# avr_programming_shield_v2.net
KiCad netlist of a schematic drawn in EAGLE
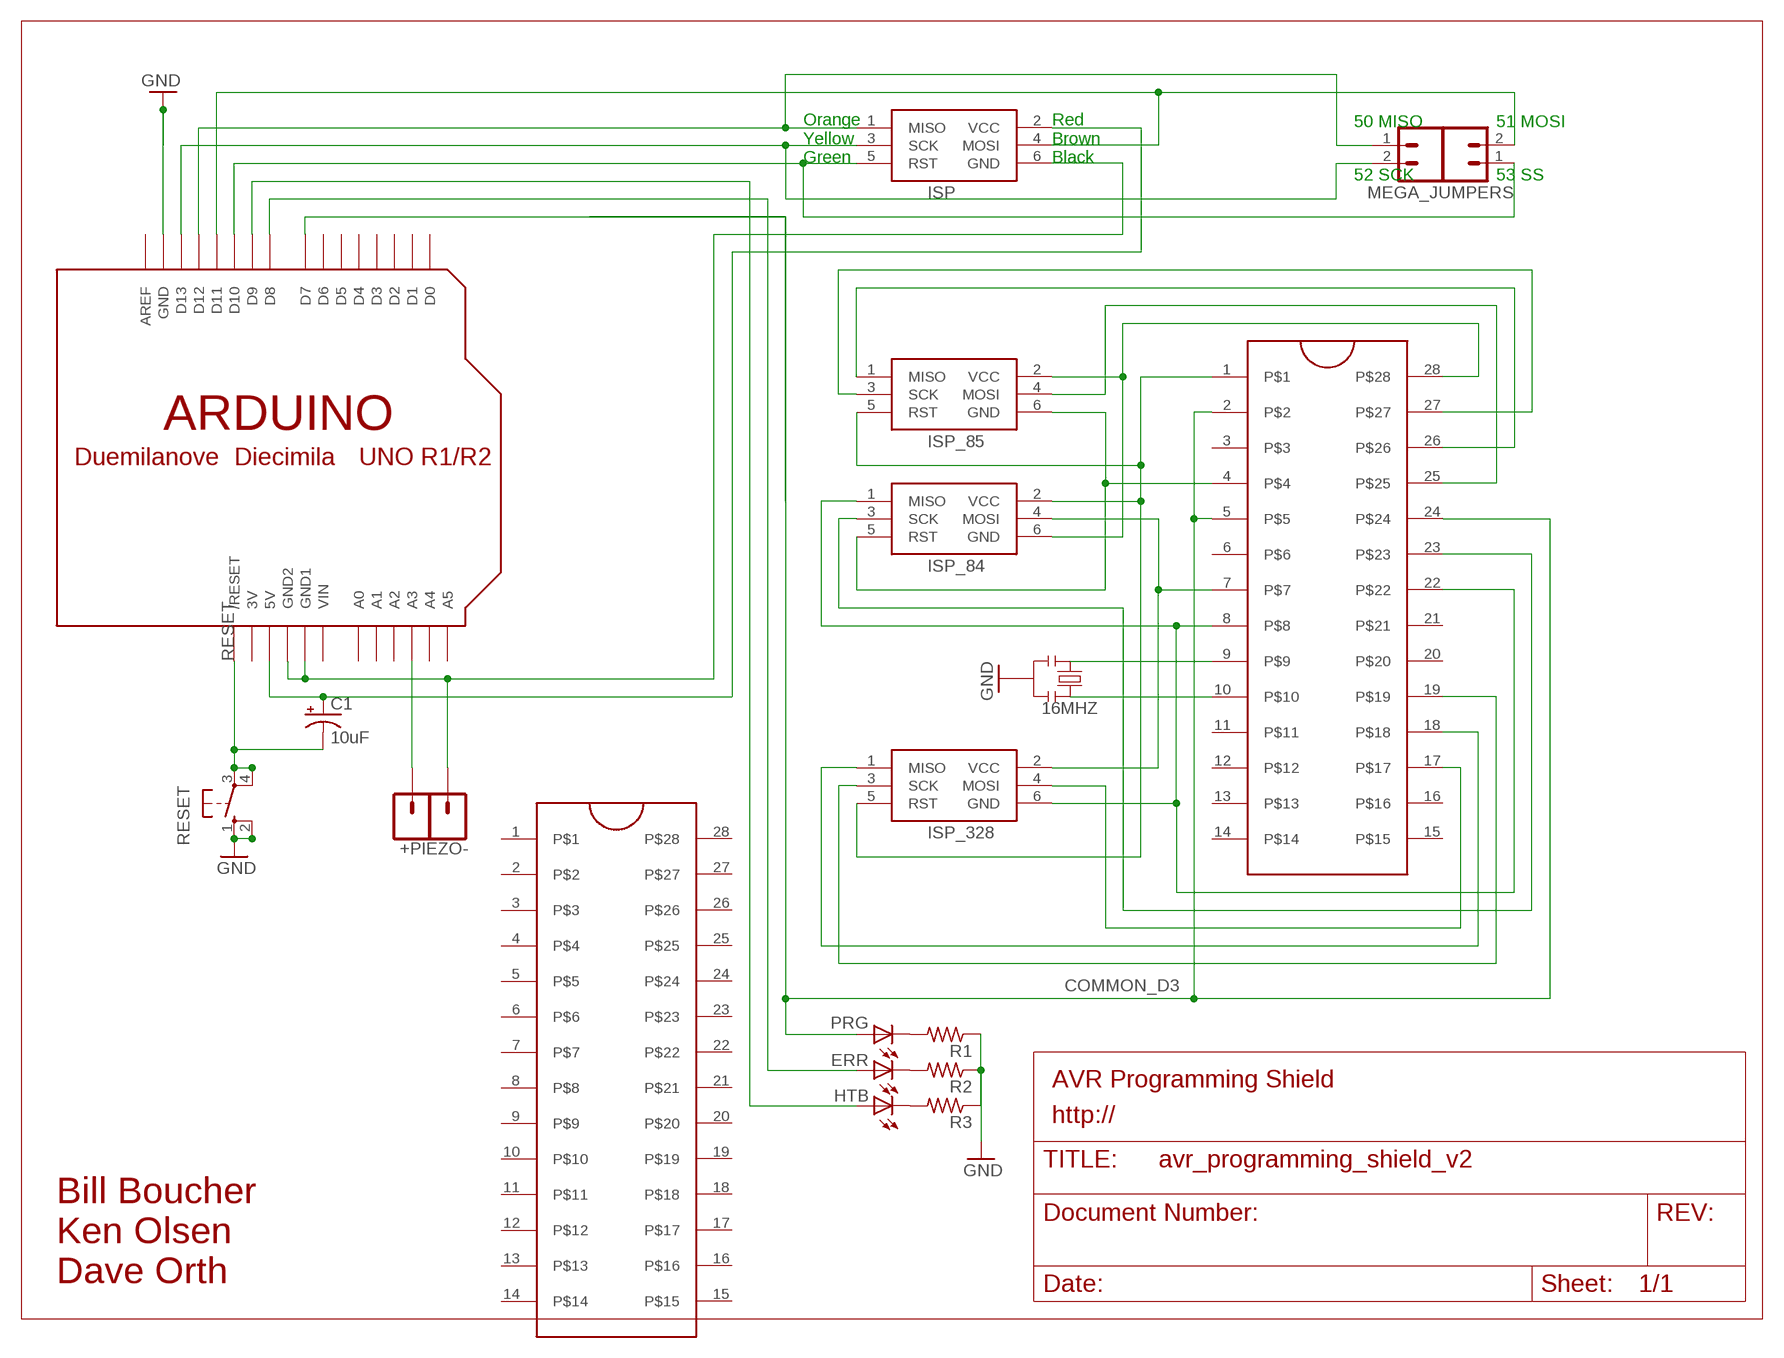
[diagram p0: schematic, sheet 1]

(export (version "E")
  (design (tool "Eeschema 10.0.6"))
  (components
    (comp (ref "+PIEZO-")
      (value "M01PTH")
      (footprint "eagle-import:1X01")
      (libsource (lib "eagle-import") (part "M01PTH"))
    )
    (comp (ref "16MHZ")
      (value "RESONATORPTH")
      (footprint "eagle-import:RESONATOR-PTH")
      (libsource (lib "eagle-import") (part "RESONATORPTH"))
    )
    (comp (ref "C1")
      (value "10uF")
      (footprint "eagle-import:CPOL-RADIAL-10UF-25V")
      (fields (field (name "MF") "ILLINOIS CAPACITOR,INC.") (field (name "MPN") "106TTA035M"))
      (libsource (lib "eagle-import") (part "CAP_POLPTH2"))
    )
    (comp (ref "ERR")
      (value "LED3MM")
      (footprint "eagle-import:LED3MM")
      (libsource (lib "eagle-import") (part "LED3MM"))
    )
    (comp (ref "HTB")
      (value "LED3MM")
      (footprint "eagle-import:LED3MM")
      (libsource (lib "eagle-import") (part "LED3MM"))
    )
    (comp (ref "ISP")
      (value "AVRISP-6")
      (footprint "eagle-import:AVRISP")
      (libsource (lib "eagle-import") (part "AVRISP-6"))
    )
    (comp (ref "ISP_84")
      (value "AVRISP-6")
      (footprint "eagle-import:AVRISP")
      (libsource (lib "eagle-import") (part "AVRISP-6"))
    )
    (comp (ref "ISP_85")
      (value "AVRISP-6")
      (footprint "eagle-import:AVRISP")
      (libsource (lib "eagle-import") (part "AVRISP-6"))
    )
    (comp (ref "ISP_328")
      (value "AVRISP-6")
      (footprint "eagle-import:AVRISP")
      (libsource (lib "eagle-import") (part "AVRISP-6"))
    )
    (comp (ref "JP2")
      (value "M02PTH")
      (footprint "eagle-import:1X02")
      (libsource (lib "eagle-import") (part "M02PTH"))
    )
    (comp (ref "JP4")
      (value "M01PTH")
      (footprint "eagle-import:1X01")
      (libsource (lib "eagle-import") (part "M01PTH"))
    )
    (comp (ref "MEGA_JUMPERS")
      (value "M02PTH")
      (footprint "eagle-import:1X02")
      (libsource (lib "eagle-import") (part "M02PTH"))
    )
    (comp (ref "PRG")
      (value "LED3MM")
      (footprint "eagle-import:LED3MM")
      (libsource (lib "eagle-import") (part "LED3MM"))
    )
    (comp (ref "R1")
      (value "R-US_0204/2V")
      (footprint "eagle-import:0204V")
      (libsource (lib "eagle-import") (part "R-US_0204/2V"))
    )
    (comp (ref "R2")
      (value "R-US_0204/2V")
      (footprint "eagle-import:0204V")
      (libsource (lib "eagle-import") (part "R-US_0204/2V"))
    )
    (comp (ref "R3")
      (value "R-US_0204/2V")
      (footprint "eagle-import:0204V")
      (libsource (lib "eagle-import") (part "R-US_0204/2V"))
    )
    (comp (ref "RESET")
      (value "10-XX")
      (footprint "eagle-import:B3F-10XX")
      (fields
        (field (name "MPN") "B3F-1000")
        (field (name "MPN_1") "B3F-1000")
        (field (name "OC_NEWARK") "36M3542")
      )
      (libsource (lib "eagle-import") (part "10-XX"))
    )
    (comp (ref "U$1")
      (value "ARDUINO-NOHOLE")
      (footprint "eagle-import:ARDUINO-NOHOLE")
      (libsource (lib "eagle-import") (part "ARDUINO-NOHOLE"))
    )
    (comp (ref "U$3")
      (value "ZIFSOCKET-28-3ZIFFSOCKET-28-3")
      (footprint "eagle-import:DIL28-3-ZIF_SOCKET")
      (libsource (lib "eagle-import") (part "ZIFSOCKET-28-3ZIFFSOCKET-28-3"))
    )
    (comp (ref "U$4")
      (value "ZIFSOCKET-28-3ZIFFSOCKET-28-3")
      (footprint "eagle-import:DIL28-3-ZIF_SOCKET")
      (libsource (lib "eagle-import") (part "SparkFun_mod_ZIFSOCKET-28-3ZIFFSOCKET-28-3"))
    )
  )
  (nets
    (net (code "1") (name "/3V") (class "Default")
      (node (ref "U$1") (pin "3V") (pinfunction "3V_3V") (pintype "power_in"))
    )
    (net (code "2") (name "/COMMON_D3") (class "Default")
      (node (ref "PRG") (pin "A") (pinfunction "A_A") (pintype "passive"))
      (node (ref "U$1") (pin "D7") (pinfunction "D7_D7") (pintype "bidirectional"))
      (node (ref "U$4") (pin "2") (pinfunction "P$2_2") (pintype "bidirectional"))
      (node (ref "U$4") (pin "24") (pinfunction "P$24_24") (pintype "bidirectional"))
      (node (ref "U$4") (pin "5") (pinfunction "P$5_5") (pintype "bidirectional"))
    )
    (net (code "3") (name "/RESET") (class "Default")
      (node (ref "C1") (pin "2") (pinfunction "-_2") (pintype "passive"))
      (node (ref "RESET") (pin "3") (pinfunction "P_3") (pintype "passive"))
      (node (ref "RESET") (pin "4") (pinfunction "P1_4") (pintype "passive"))
      (node (ref "U$1") (pin "RESET") (pinfunction "/RESET_RESET") (pintype "bidirectional"))
    )
    (net (code "4") (name "/VIN") (class "Default")
      (node (ref "U$1") (pin "VIN") (pinfunction "VIN_VIN") (pintype "power_in"))
    )
    (net (code "5") (name "GND") (class "Default")
      (node (ref "+PIEZO-") (pin "1") (pinfunction "1_1") (pintype "passive"))
      (node (ref "16MHZ") (pin "2") (pinfunction "2_2") (pintype "passive"))
      (node (ref "ISP") (pin "6") (pinfunction "GND_6") (pintype "power_in"))
      (node (ref "R1") (pin "1") (pinfunction "1_1") (pintype "passive"))
      (node (ref "R2") (pin "1") (pinfunction "1_1") (pintype "passive"))
      (node (ref "R3") (pin "1") (pinfunction "1_1") (pintype "passive"))
      (node (ref "RESET") (pin "1") (pinfunction "S_1") (pintype "passive"))
      (node (ref "RESET") (pin "2") (pinfunction "S1_2") (pintype "passive"))
      (node (ref "U$1") (pin "GND") (pinfunction "GND_GND") (pintype "power_in"))
      (node (ref "U$1") (pin "GND1") (pinfunction "GND1_GND1") (pintype "power_in"))
      (node (ref "U$1") (pin "GND2") (pinfunction "GND2_GND2") (pintype "power_in"))
    )
    (net (code "6") (name "Net-(C1-+)") (class "Default")
      (node (ref "C1") (pin "1") (pinfunction "+_1") (pintype "passive"))
      (node (ref "ISP") (pin "2") (pinfunction "VCC_2") (pintype "power_in"))
      (node (ref "U$1") (pin "5V") (pinfunction "5V_5V") (pintype "power_in"))
    )
    (net (code "7") (name "Net-(ERR-C)") (class "Default")
      (node (ref "ERR") (pin "K") (pinfunction "C_K") (pintype "passive"))
      (node (ref "R2") (pin "2") (pinfunction "2_2") (pintype "passive"))
    )
    (net (code "8") (name "Net-(ERR-PadA)") (class "Default")
      (node (ref "ERR") (pin "A") (pinfunction "A_A") (pintype "passive"))
      (node (ref "U$1") (pin "D8") (pinfunction "D8_D8") (pintype "bidirectional"))
    )
    (net (code "9") (name "Net-(HTB-C)") (class "Default")
      (node (ref "HTB") (pin "K") (pinfunction "C_K") (pintype "passive"))
      (node (ref "R3") (pin "2") (pinfunction "2_2") (pintype "passive"))
    )
    (net (code "10") (name "Net-(HTB-PadA)") (class "Default")
      (node (ref "HTB") (pin "A") (pinfunction "A_A") (pintype "passive"))
      (node (ref "U$1") (pin "D9") (pinfunction "D9_D9") (pintype "bidirectional"))
    )
    (net (code "11") (name "Net-(ISP-MISO)") (class "Default")
      (node (ref "ISP") (pin "1") (pinfunction "MISO_1") (pintype "input"))
      (node (ref "MEGA_JUMPERS") (pin "1") (pinfunction "1_1") (pintype "passive"))
      (node (ref "U$1") (pin "D12") (pinfunction "D12_D12") (pintype "bidirectional"))
    )
    (net (code "12") (name "Net-(ISP-MOSI)") (class "Default")
      (node (ref "ISP") (pin "4") (pinfunction "MOSI_4") (pintype "output"))
      (node (ref "JP2") (pin "2") (pinfunction "2_2") (pintype "passive"))
      (node (ref "U$1") (pin "D11") (pinfunction "D11_D11") (pintype "bidirectional"))
    )
    (net (code "13") (name "Net-(ISP-RST)") (class "Default")
      (node (ref "ISP") (pin "5") (pinfunction "RST_5") (pintype "output"))
      (node (ref "JP2") (pin "1") (pinfunction "1_1") (pintype "passive"))
      (node (ref "U$1") (pin "D10") (pinfunction "D10_D10") (pintype "bidirectional"))
    )
    (net (code "14") (name "Net-(ISP-SCK)") (class "Default")
      (node (ref "ISP") (pin "3") (pinfunction "SCK_3") (pintype "output"))
      (node (ref "MEGA_JUMPERS") (pin "2") (pinfunction "2_2") (pintype "passive"))
      (node (ref "U$1") (pin "D13") (pinfunction "D13_D13") (pintype "bidirectional"))
    )
    (net (code "15") (name "Net-(ISP_84-GND)") (class "Default")
      (node (ref "ISP_84") (pin "6") (pinfunction "GND_6") (pintype "power_in"))
      (node (ref "ISP_85") (pin "2") (pinfunction "VCC_2") (pintype "power_in"))
      (node (ref "U$4") (pin "28") (pinfunction "P$28_28") (pintype "bidirectional"))
    )
    (net (code "16") (name "Net-(ISP_84-RST)") (class "Default")
      (node (ref "ISP_84") (pin "5") (pinfunction "RST_5") (pintype "output"))
      (node (ref "ISP_85") (pin "6") (pinfunction "GND_6") (pintype "power_in"))
      (node (ref "U$4") (pin "4") (pinfunction "P$4_4") (pintype "bidirectional"))
    )
    (net (code "17") (name "Net-(ISP_84-SCK)") (class "Default")
      (node (ref "ISP_84") (pin "3") (pinfunction "SCK_3") (pintype "output"))
      (node (ref "U$4") (pin "23") (pinfunction "P$23_23") (pintype "bidirectional"))
    )
    (net (code "18") (name "Net-(ISP_85-MISO)") (class "Default")
      (node (ref "ISP_85") (pin "1") (pinfunction "MISO_1") (pintype "input"))
      (node (ref "U$4") (pin "26") (pinfunction "P$26_26") (pintype "bidirectional"))
    )
    (net (code "19") (name "Net-(ISP_85-MOSI)") (class "Default")
      (node (ref "ISP_85") (pin "4") (pinfunction "MOSI_4") (pintype "output"))
      (node (ref "U$4") (pin "25") (pinfunction "P$25_25") (pintype "bidirectional"))
    )
    (net (code "20") (name "Net-(ISP_85-SCK)") (class "Default")
      (node (ref "ISP_85") (pin "3") (pinfunction "SCK_3") (pintype "output"))
      (node (ref "U$4") (pin "27") (pinfunction "P$27_27") (pintype "bidirectional"))
    )
    (net (code "21") (name "Net-(ISP_328-GND)") (class "Default")
      (node (ref "ISP_328") (pin "6") (pinfunction "GND_6") (pintype "power_in"))
      (node (ref "ISP_84") (pin "1") (pinfunction "MISO_1") (pintype "input"))
      (node (ref "U$4") (pin "22") (pinfunction "P$22_22") (pintype "bidirectional"))
      (node (ref "U$4") (pin "8") (pinfunction "P$8_8") (pintype "bidirectional"))
    )
    (net (code "22") (name "Net-(ISP_328-MISO)") (class "Default")
      (node (ref "ISP_328") (pin "1") (pinfunction "MISO_1") (pintype "input"))
      (node (ref "U$4") (pin "18") (pinfunction "P$18_18") (pintype "bidirectional"))
    )
    (net (code "23") (name "Net-(ISP_328-MOSI)") (class "Default")
      (node (ref "ISP_328") (pin "4") (pinfunction "MOSI_4") (pintype "output"))
      (node (ref "U$4") (pin "17") (pinfunction "P$17_17") (pintype "bidirectional"))
    )
    (net (code "24") (name "Net-(ISP_328-RST)") (class "Default")
      (node (ref "ISP_328") (pin "5") (pinfunction "RST_5") (pintype "output"))
      (node (ref "ISP_84") (pin "2") (pinfunction "VCC_2") (pintype "power_in"))
      (node (ref "ISP_85") (pin "5") (pinfunction "RST_5") (pintype "output"))
      (node (ref "U$4") (pin "1") (pinfunction "P$1_1") (pintype "bidirectional"))
    )
    (net (code "25") (name "Net-(ISP_328-SCK)") (class "Default")
      (node (ref "ISP_328") (pin "3") (pinfunction "SCK_3") (pintype "output"))
      (node (ref "U$4") (pin "19") (pinfunction "P$19_19") (pintype "bidirectional"))
    )
    (net (code "26") (name "Net-(ISP_328-VCC)") (class "Default")
      (node (ref "ISP_328") (pin "2") (pinfunction "VCC_2") (pintype "power_in"))
      (node (ref "ISP_84") (pin "4") (pinfunction "MOSI_4") (pintype "output"))
      (node (ref "U$4") (pin "7") (pinfunction "P$7_7") (pintype "bidirectional"))
    )
    (net (code "27") (name "Net-(JP4-Pad1)") (class "Default")
      (node (ref "JP4") (pin "1") (pinfunction "1_1") (pintype "passive"))
      (node (ref "U$1") (pin "A3") (pinfunction "A3_A3") (pintype "bidirectional"))
    )
    (net (code "28") (name "Net-(PRG-C)") (class "Default")
      (node (ref "PRG") (pin "K") (pinfunction "C_K") (pintype "passive"))
      (node (ref "R1") (pin "2") (pinfunction "2_2") (pintype "passive"))
    )
    (net (code "29") (name "Net-(U$4-P$9)") (class "Default")
      (node (ref "16MHZ") (pin "1") (pinfunction "1_1") (pintype "passive"))
      (node (ref "U$4") (pin "9") (pinfunction "P$9_9") (pintype "bidirectional"))
    )
    (net (code "30") (name "Net-(U$4-P$10)") (class "Default")
      (node (ref "16MHZ") (pin "3") (pinfunction "3_3") (pintype "passive"))
      (node (ref "U$4") (pin "10") (pinfunction "P$10_10") (pintype "bidirectional"))
    )
    (net (code "31") (name "unconnected-(U$1-PadA0)") (class "Default")
      (node (ref "U$1") (pin "A0") (pinfunction "A0_A0") (pintype "bidirectional"))
    )
    (net (code "32") (name "unconnected-(U$1-PadA1)") (class "Default")
      (node (ref "U$1") (pin "A1") (pinfunction "A1_A1") (pintype "bidirectional"))
    )
    (net (code "33") (name "unconnected-(U$1-PadA2)") (class "Default")
      (node (ref "U$1") (pin "A2") (pinfunction "A2_A2") (pintype "bidirectional"))
    )
    (net (code "34") (name "unconnected-(U$1-PadA4)") (class "Default")
      (node (ref "U$1") (pin "A4") (pinfunction "A4_A4") (pintype "bidirectional"))
    )
    (net (code "35") (name "unconnected-(U$1-PadA5)") (class "Default")
      (node (ref "U$1") (pin "A5") (pinfunction "A5_A5") (pintype "bidirectional"))
    )
    (net (code "36") (name "unconnected-(U$1-PadAREF)") (class "Default")
      (node (ref "U$1") (pin "AREF") (pinfunction "AREF_AREF") (pintype "bidirectional"))
    )
    (net (code "37") (name "unconnected-(U$1-PadD0)") (class "Default")
      (node (ref "U$1") (pin "D0") (pinfunction "D0_D0") (pintype "bidirectional"))
    )
    (net (code "38") (name "unconnected-(U$1-PadD1)") (class "Default")
      (node (ref "U$1") (pin "D1") (pinfunction "D1_D1") (pintype "bidirectional"))
    )
    (net (code "39") (name "unconnected-(U$1-PadD2)") (class "Default")
      (node (ref "U$1") (pin "D2") (pinfunction "D2_D2") (pintype "bidirectional"))
    )
    (net (code "40") (name "unconnected-(U$1-PadD3)") (class "Default")
      (node (ref "U$1") (pin "D3") (pinfunction "D3_D3") (pintype "bidirectional"))
    )
    (net (code "41") (name "unconnected-(U$1-PadD4)") (class "Default")
      (node (ref "U$1") (pin "D4") (pinfunction "D4_D4") (pintype "bidirectional"))
    )
    (net (code "42") (name "unconnected-(U$1-PadD5)") (class "Default")
      (node (ref "U$1") (pin "D5") (pinfunction "D5_D5") (pintype "bidirectional"))
    )
    (net (code "43") (name "unconnected-(U$1-PadD6)") (class "Default")
      (node (ref "U$1") (pin "D6") (pinfunction "D6_D6") (pintype "bidirectional"))
    )
    (net (code "44") (name "unconnected-(U$3-P$1-Pad1)") (class "Default")
      (node (ref "U$3") (pin "1") (pinfunction "P$1_1") (pintype "bidirectional"))
    )
    (net (code "45") (name "unconnected-(U$3-P$2-Pad2)") (class "Default")
      (node (ref "U$3") (pin "2") (pinfunction "P$2_2") (pintype "bidirectional"))
    )
    (net (code "46") (name "unconnected-(U$3-P$3-Pad3)") (class "Default")
      (node (ref "U$3") (pin "3") (pinfunction "P$3_3") (pintype "bidirectional"))
    )
    (net (code "47") (name "unconnected-(U$3-P$4-Pad4)") (class "Default")
      (node (ref "U$3") (pin "4") (pinfunction "P$4_4") (pintype "bidirectional"))
    )
    (net (code "48") (name "unconnected-(U$3-P$5-Pad5)") (class "Default")
      (node (ref "U$3") (pin "5") (pinfunction "P$5_5") (pintype "bidirectional"))
    )
    (net (code "49") (name "unconnected-(U$3-P$6-Pad6)") (class "Default")
      (node (ref "U$3") (pin "6") (pinfunction "P$6_6") (pintype "bidirectional"))
    )
    (net (code "50") (name "unconnected-(U$3-P$7-Pad7)") (class "Default")
      (node (ref "U$3") (pin "7") (pinfunction "P$7_7") (pintype "bidirectional"))
    )
    (net (code "51") (name "unconnected-(U$3-P$8-Pad8)") (class "Default")
      (node (ref "U$3") (pin "8") (pinfunction "P$8_8") (pintype "bidirectional"))
    )
    (net (code "52") (name "unconnected-(U$3-P$9-Pad9)") (class "Default")
      (node (ref "U$3") (pin "9") (pinfunction "P$9_9") (pintype "bidirectional"))
    )
    (net (code "53") (name "unconnected-(U$3-P$10-Pad10)") (class "Default")
      (node (ref "U$3") (pin "10") (pinfunction "P$10_10") (pintype "bidirectional"))
    )
    (net (code "54") (name "unconnected-(U$3-P$11-Pad11)") (class "Default")
      (node (ref "U$3") (pin "11") (pinfunction "P$11_11") (pintype "bidirectional"))
    )
    (net (code "55") (name "unconnected-(U$3-P$12-Pad12)") (class "Default")
      (node (ref "U$3") (pin "12") (pinfunction "P$12_12") (pintype "bidirectional"))
    )
    (net (code "56") (name "unconnected-(U$3-P$13-Pad13)") (class "Default")
      (node (ref "U$3") (pin "13") (pinfunction "P$13_13") (pintype "bidirectional"))
    )
    (net (code "57") (name "unconnected-(U$3-P$14-Pad14)") (class "Default")
      (node (ref "U$3") (pin "14") (pinfunction "P$14_14") (pintype "bidirectional"))
    )
    (net (code "58") (name "unconnected-(U$3-P$15-Pad15)") (class "Default")
      (node (ref "U$3") (pin "15") (pinfunction "P$15_15") (pintype "bidirectional"))
    )
    (net (code "59") (name "unconnected-(U$3-P$16-Pad16)") (class "Default")
      (node (ref "U$3") (pin "16") (pinfunction "P$16_16") (pintype "bidirectional"))
    )
    (net (code "60") (name "unconnected-(U$3-P$17-Pad17)") (class "Default")
      (node (ref "U$3") (pin "17") (pinfunction "P$17_17") (pintype "bidirectional"))
    )
    (net (code "61") (name "unconnected-(U$3-P$18-Pad18)") (class "Default")
      (node (ref "U$3") (pin "18") (pinfunction "P$18_18") (pintype "bidirectional"))
    )
    (net (code "62") (name "unconnected-(U$3-P$19-Pad19)") (class "Default")
      (node (ref "U$3") (pin "19") (pinfunction "P$19_19") (pintype "bidirectional"))
    )
    (net (code "63") (name "unconnected-(U$3-P$20-Pad20)") (class "Default")
      (node (ref "U$3") (pin "20") (pinfunction "P$20_20") (pintype "bidirectional"))
    )
    (net (code "64") (name "unconnected-(U$3-P$21-Pad21)") (class "Default")
      (node (ref "U$3") (pin "21") (pinfunction "P$21_21") (pintype "bidirectional"))
    )
    (net (code "65") (name "unconnected-(U$3-P$22-Pad22)") (class "Default")
      (node (ref "U$3") (pin "22") (pinfunction "P$22_22") (pintype "bidirectional"))
    )
    (net (code "66") (name "unconnected-(U$3-P$23-Pad23)") (class "Default")
      (node (ref "U$3") (pin "23") (pinfunction "P$23_23") (pintype "bidirectional"))
    )
    (net (code "67") (name "unconnected-(U$3-P$24-Pad24)") (class "Default")
      (node (ref "U$3") (pin "24") (pinfunction "P$24_24") (pintype "bidirectional"))
    )
    (net (code "68") (name "unconnected-(U$3-P$25-Pad25)") (class "Default")
      (node (ref "U$3") (pin "25") (pinfunction "P$25_25") (pintype "bidirectional"))
    )
    (net (code "69") (name "unconnected-(U$3-P$26-Pad26)") (class "Default")
      (node (ref "U$3") (pin "26") (pinfunction "P$26_26") (pintype "bidirectional"))
    )
    (net (code "70") (name "unconnected-(U$3-P$27-Pad27)") (class "Default")
      (node (ref "U$3") (pin "27") (pinfunction "P$27_27") (pintype "bidirectional"))
    )
    (net (code "71") (name "unconnected-(U$3-P$28-Pad28)") (class "Default")
      (node (ref "U$3") (pin "28") (pinfunction "P$28_28") (pintype "bidirectional"))
    )
    (net (code "72") (name "unconnected-(U$4-P$3-Pad3)") (class "Default")
      (node (ref "U$4") (pin "3") (pinfunction "P$3_3") (pintype "bidirectional"))
    )
    (net (code "73") (name "unconnected-(U$4-P$6-Pad6)") (class "Default")
      (node (ref "U$4") (pin "6") (pinfunction "P$6_6") (pintype "bidirectional"))
    )
    (net (code "74") (name "unconnected-(U$4-P$11-Pad11)") (class "Default")
      (node (ref "U$4") (pin "11") (pinfunction "P$11_11") (pintype "bidirectional"))
    )
    (net (code "75") (name "unconnected-(U$4-P$12-Pad12)") (class "Default")
      (node (ref "U$4") (pin "12") (pinfunction "P$12_12") (pintype "bidirectional"))
    )
    (net (code "76") (name "unconnected-(U$4-P$13-Pad13)") (class "Default")
      (node (ref "U$4") (pin "13") (pinfunction "P$13_13") (pintype "bidirectional"))
    )
    (net (code "77") (name "unconnected-(U$4-P$14-Pad14)") (class "Default")
      (node (ref "U$4") (pin "14") (pinfunction "P$14_14") (pintype "bidirectional"))
    )
    (net (code "78") (name "unconnected-(U$4-P$15-Pad15)") (class "Default")
      (node (ref "U$4") (pin "15") (pinfunction "P$15_15") (pintype "bidirectional"))
    )
    (net (code "79") (name "unconnected-(U$4-P$16-Pad16)") (class "Default")
      (node (ref "U$4") (pin "16") (pinfunction "P$16_16") (pintype "bidirectional"))
    )
    (net (code "80") (name "unconnected-(U$4-P$20-Pad20)") (class "Default")
      (node (ref "U$4") (pin "20") (pinfunction "P$20_20") (pintype "bidirectional"))
    )
    (net (code "81") (name "unconnected-(U$4-P$21-Pad21)") (class "Default")
      (node (ref "U$4") (pin "21") (pinfunction "P$21_21") (pintype "bidirectional"))
    )
  )
)
